# RGB_LED_Board_--_Breadboard_Version_--_S.net
KiCad netlist of a schematic drawn in EAGLE
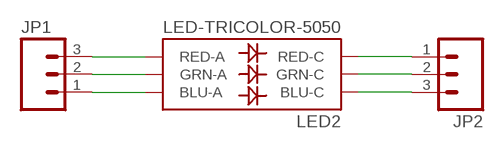
[diagram p0: schematic, sheet 1]

(export (version "E")
  (design (tool "Eeschema 10.0.6"))
  (components
    (comp (ref "JP1")
      (value "M03PTH")
      (footprint "eagle-import:1X03")
      (libsource (lib "eagle-import") (part "M03PTH"))
    )
    (comp (ref "JP2")
      (value "M03PTH")
      (footprint "eagle-import:1X03")
      (libsource (lib "eagle-import") (part "M03PTH"))
    )
    (comp (ref "LED2")
      (value "LED-TRICOLOR-5050")
      (footprint "eagle-import:LED-TRICOLOR-5050")
      (libsource (lib "eagle-import") (part "LED-TRICOLOR-5050"))
    )
  )
  (nets
    (net (code "1") (name "Net-(LED2-BLU-A)") (class "Default")
      (node (ref "JP1") (pin "1") (pinfunction "1_1") (pintype "passive"))
      (node (ref "LED2") (pin "3") (pinfunction "BLU-A_3") (pintype "bidirectional"))
    )
    (net (code "2") (name "Net-(LED2-BLU-C)") (class "Default")
      (node (ref "JP2") (pin "3") (pinfunction "3_3") (pintype "passive"))
      (node (ref "LED2") (pin "4") (pinfunction "BLU-C_4") (pintype "bidirectional"))
    )
    (net (code "3") (name "Net-(LED2-GRN-A)") (class "Default")
      (node (ref "JP1") (pin "2") (pinfunction "2_2") (pintype "passive"))
      (node (ref "LED2") (pin "1") (pinfunction "GRN-A_1") (pintype "bidirectional"))
    )
    (net (code "4") (name "Net-(LED2-GRN-C)") (class "Default")
      (node (ref "JP2") (pin "2") (pinfunction "2_2") (pintype "passive"))
      (node (ref "LED2") (pin "6") (pinfunction "GRN-C_6") (pintype "bidirectional"))
    )
    (net (code "5") (name "Net-(LED2-RED-A)") (class "Default")
      (node (ref "JP1") (pin "3") (pinfunction "3_3") (pintype "passive"))
      (node (ref "LED2") (pin "2") (pinfunction "RED-A_2") (pintype "bidirectional"))
    )
    (net (code "6") (name "Net-(LED2-RED-C)") (class "Default")
      (node (ref "JP2") (pin "1") (pinfunction "1_1") (pintype "passive"))
      (node (ref "LED2") (pin "5") (pinfunction "RED-C_5") (pintype "bidirectional"))
    )
  )
)
